# 1-Schematic_biz-card.net
KiCad netlist of a schematic drawn in EasyEDA
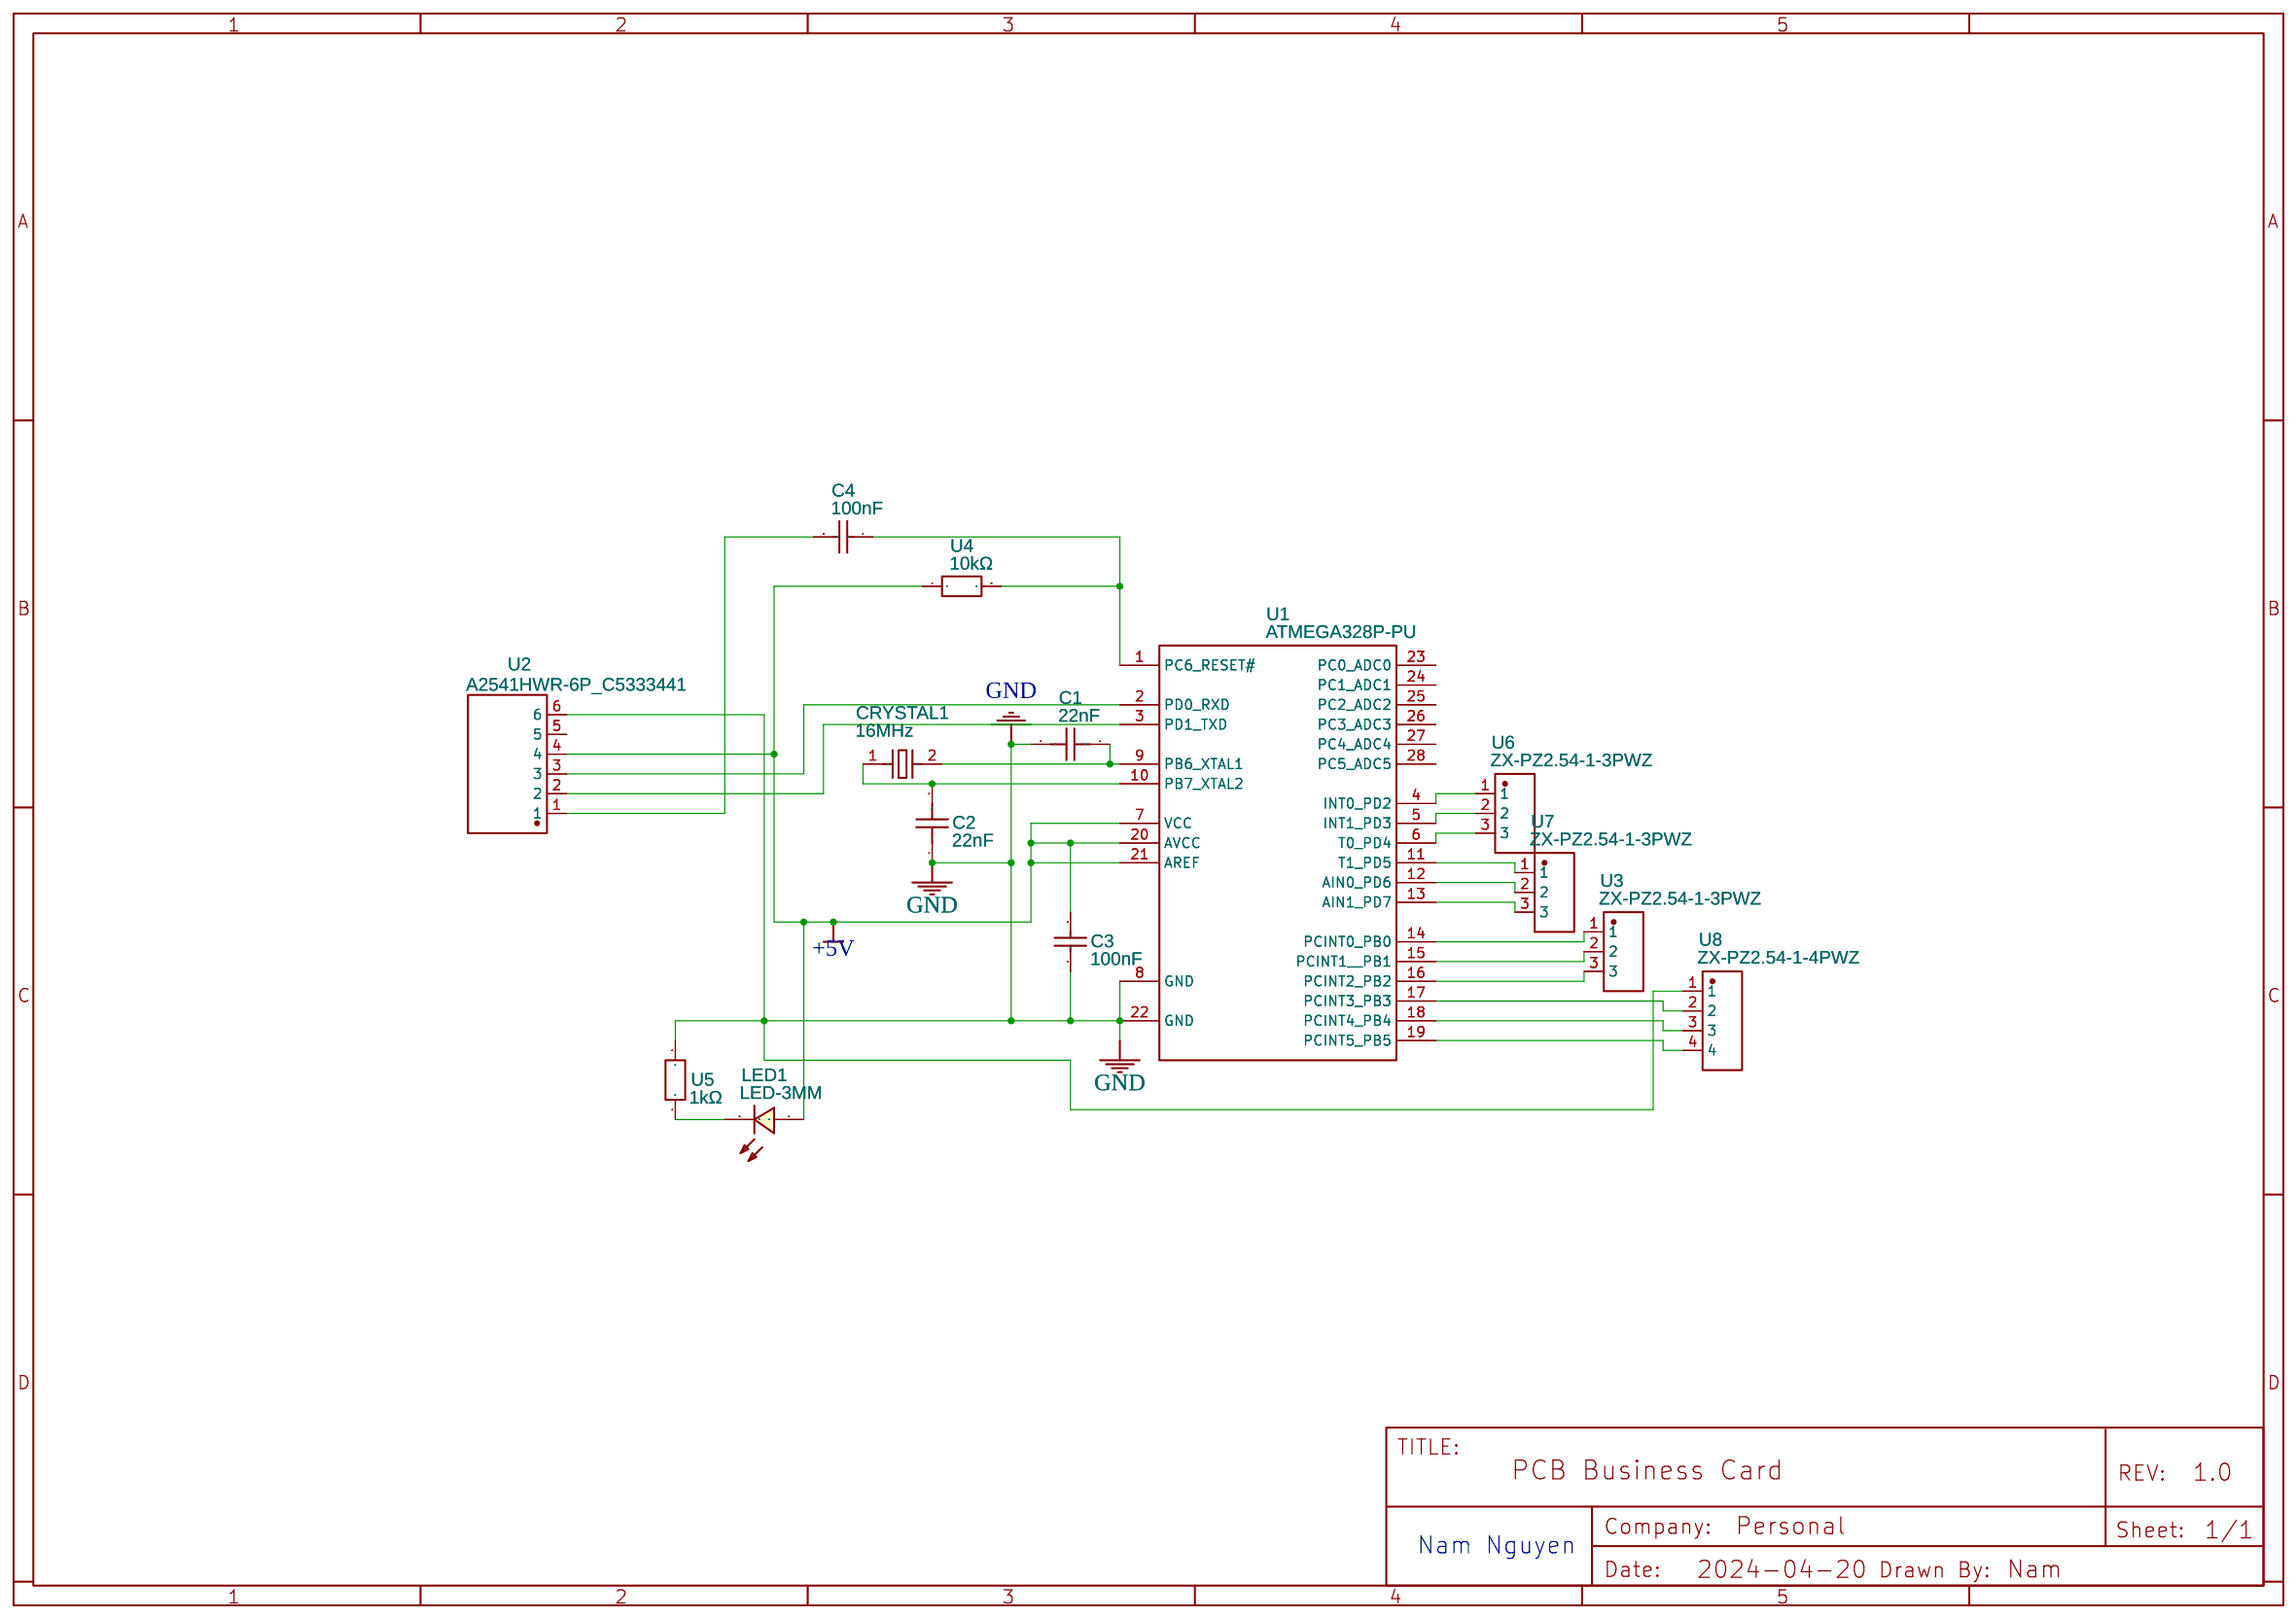
[diagram p0: schematic sheet]

(export (version "E")
  (design (tool "Eeschema 10.0.6"))
  (components
    (comp (ref "C1")
      (value "22nF")
      (fields
        (field (name "Manufacturer Part") "CC1H223ZC1SD3F4D30MF")
        (field (name "Manufacturer") "Dersonic(德尔创)")
      )
      (libsource (lib "") (part "CC1H223ZC1SD3F4D30MF_1"))
    )
    (comp (ref "C2")
      (value "22nF")
      (fields
        (field (name "Manufacturer Part") "CC1H223ZC1SD3F4D30MF")
        (field (name "Manufacturer") "Dersonic(德尔创)")
      )
      (libsource (lib "") (part "CC1H223ZC1SD3F4D30MF"))
    )
    (comp (ref "C3")
      (value "100nF")
      (fields (field (name "Manufacturer Part") "0.1UF(104) +-20% 63v"))
      (libsource (lib "") (part "100nF_1"))
    )
    (comp (ref "C4")
      (value "100nF")
      (fields (field (name "Manufacturer Part") "0.1UF(104) +-20% 63v"))
      (libsource (lib "") (part "100nF"))
    )
    (comp (ref "CRYSTAL1")
      (value "16MHz")
      (fields (field (name "Manufacturer Part") "SP2016M00020001") (field (name "Manufacturer") "HUAXIN(华昕)"))
      (libsource (lib "") (part "SP2016M00020001"))
    )
    (comp (ref "LED1")
      (value "LED-3MM")
      (fields (field (name "Manufacturer Part") "LED-3mm红"))
      (libsource (lib "") (part "LED-3MM红"))
    )
    (comp (ref "U1")
      (value "ATMEGA328P-PU")
      (fields (field (name "Manufacturer") "MICROCHIP(美国微芯)"))
      (libsource (lib "") (part "ATMEGA328P-PU"))
    )
    (comp (ref "U2")
      (value "A2541HWR-6P_C5333441")
      (fields (field (name "Manufacturer Part") "A2541HWR-6P") (field (name "Manufacturer") "CJT(长江连接器)"))
      (libsource (lib "") (part "A2541HWR-6P_C5333441"))
    )
    (comp (ref "U3")
      (value "ZX-PZ2.54-1-3PWZ")
      (fields (field (name "Manufacturer") "Megastar(兆星)"))
      (libsource (lib "") (part "ZX-PZ2.54-1-3PWZ"))
    )
    (comp (ref "U4")
      (value "10kΩ")
      (fields
        (field (name "Manufacturer Part") "RNS1FTD10K0")
        (field (name "Manufacturer") "SEI(Stackpole Electronics Inc.)")
      )
      (libsource (lib "") (part "RNS1FTD10K0"))
    )
    (comp (ref "U5")
      (value "1kΩ")
      (fields
        (field (name "Manufacturer Part") "MRS25000C1001FCT00")
        (field (name "Manufacturer") "VISHAY(威世)")
      )
      (libsource (lib "") (part "MRS25000C1001FCT00"))
    )
    (comp (ref "U6")
      (value "ZX-PZ2.54-1-3PWZ")
      (fields (field (name "Manufacturer") "Megastar(兆星)"))
      (libsource (lib "") (part "ZX-PZ2.54-1-3PWZ"))
    )
    (comp (ref "U7")
      (value "ZX-PZ2.54-1-3PWZ")
      (fields (field (name "Manufacturer") "Megastar(兆星)"))
      (libsource (lib "") (part "ZX-PZ2.54-1-3PWZ"))
    )
    (comp (ref "U8")
      (value "ZX-PZ2.54-1-4PWZ")
      (fields (field (name "Manufacturer") "Megastar(兆星)"))
      (libsource (lib "") (part "ZX-PZ2.54-1-4PWZ"))
    )
  )
  (nets
    (net (code "1") (name "+5V") (class "Default")
      (node (ref "C3") (pin "2") (pinfunction "2_2") (pintype "input"))
      (node (ref "LED1") (pin "1") (pinfunction "1_1") (pintype "unspecified"))
      (node (ref "U1") (pin "20") (pinfunction "AVCC_20") (pintype "passive"))
      (node (ref "U1") (pin "21") (pinfunction "AREF_21") (pintype "passive"))
      (node (ref "U1") (pin "7") (pinfunction "VCC_7") (pintype "passive"))
      (node (ref "U2") (pin "4") (pinfunction "4_4") (pintype "unspecified"))
      (node (ref "U4") (pin "1") (pinfunction "1_1") (pintype "unspecified"))
    )
    (net (code "2") (name "GND") (class "Default")
      (node (ref "C1") (pin "2") (pinfunction "2_2") (pintype "unspecified"))
      (node (ref "C2") (pin "1") (pinfunction "1_1") (pintype "unspecified"))
      (node (ref "C3") (pin "1") (pinfunction "1_1") (pintype "input"))
      (node (ref "U1") (pin "22") (pinfunction "GND_22") (pintype "passive"))
      (node (ref "U1") (pin "8") (pinfunction "GND_8") (pintype "passive"))
      (node (ref "U2") (pin "6") (pinfunction "6_6") (pintype "unspecified"))
      (node (ref "U5") (pin "2") (pinfunction "2_2") (pintype "unspecified"))
      (node (ref "U8") (pin "1") (pinfunction "1_1") (pintype "unspecified"))
    )
    (net (code "3") (name "Net-(C4-Pad2)") (class "Default")
      (node (ref "C4") (pin "2") (pinfunction "2_2") (pintype "input"))
      (node (ref "U2") (pin "1") (pinfunction "1_1") (pintype "unspecified"))
    )
    (net (code "4") (name "Net-(LED1-Pad2)") (class "Default")
      (node (ref "LED1") (pin "2") (pinfunction "2_2") (pintype "unspecified"))
      (node (ref "U5") (pin "1") (pinfunction "1_1") (pintype "unspecified"))
    )
    (net (code "5") (name "Net-(U1-AIN0_PD6)") (class "Default")
      (node (ref "U1") (pin "12") (pinfunction "AIN0_PD6_12") (pintype "bidirectional"))
      (node (ref "U7") (pin "2") (pinfunction "2_2") (pintype "unspecified"))
    )
    (net (code "6") (name "Net-(U1-AIN1_PD7)") (class "Default")
      (node (ref "U1") (pin "13") (pinfunction "AIN1_PD7_13") (pintype "bidirectional"))
      (node (ref "U7") (pin "3") (pinfunction "3_3") (pintype "unspecified"))
    )
    (net (code "7") (name "Net-(U1-INT0_PD2)") (class "Default")
      (node (ref "U1") (pin "4") (pinfunction "INT0_PD2_4") (pintype "bidirectional"))
      (node (ref "U6") (pin "1") (pinfunction "1_1") (pintype "unspecified"))
    )
    (net (code "8") (name "Net-(U1-INT1_PD3)") (class "Default")
      (node (ref "U1") (pin "5") (pinfunction "INT1_PD3_5") (pintype "bidirectional"))
      (node (ref "U6") (pin "2") (pinfunction "2_2") (pintype "unspecified"))
    )
    (net (code "9") (name "Net-(U1-PB6_XTAL1)") (class "Default")
      (node (ref "C1") (pin "1") (pinfunction "1_1") (pintype "unspecified"))
      (node (ref "CRYSTAL1") (pin "2") (pinfunction "2_2") (pintype "unspecified"))
      (node (ref "U1") (pin "9") (pinfunction "PB6_XTAL1_9") (pintype "bidirectional"))
    )
    (net (code "10") (name "Net-(U1-PB7_XTAL2)") (class "Default")
      (node (ref "C2") (pin "2") (pinfunction "2_2") (pintype "unspecified"))
      (node (ref "CRYSTAL1") (pin "1") (pinfunction "1_1") (pintype "unspecified"))
      (node (ref "U1") (pin "10") (pinfunction "PB7_XTAL2_10") (pintype "bidirectional"))
    )
    (net (code "11") (name "Net-(U1-PC6_RESET#)") (class "Default")
      (node (ref "C4") (pin "1") (pinfunction "1_1") (pintype "input"))
      (node (ref "U1") (pin "1") (pinfunction "PC6_RESET#_1") (pintype "bidirectional"))
      (node (ref "U4") (pin "2") (pinfunction "2_2") (pintype "unspecified"))
    )
    (net (code "12") (name "Net-(U1-PCINT0_PB0)") (class "Default")
      (node (ref "U1") (pin "14") (pinfunction "PCINT0_PB0_14") (pintype "bidirectional"))
      (node (ref "U3") (pin "1") (pinfunction "1_1") (pintype "unspecified"))
    )
    (net (code "13") (name "Net-(U1-PCINT1__PB1)") (class "Default")
      (node (ref "U1") (pin "15") (pinfunction "PCINT1__PB1_15") (pintype "bidirectional"))
      (node (ref "U3") (pin "2") (pinfunction "2_2") (pintype "unspecified"))
    )
    (net (code "14") (name "Net-(U1-PCINT2_PB2)") (class "Default")
      (node (ref "U1") (pin "16") (pinfunction "PCINT2_PB2_16") (pintype "bidirectional"))
      (node (ref "U3") (pin "3") (pinfunction "3_3") (pintype "unspecified"))
    )
    (net (code "15") (name "Net-(U1-PCINT3_PB3)") (class "Default")
      (node (ref "U1") (pin "17") (pinfunction "PCINT3_PB3_17") (pintype "bidirectional"))
      (node (ref "U8") (pin "2") (pinfunction "2_2") (pintype "unspecified"))
    )
    (net (code "16") (name "Net-(U1-PCINT4_PB4)") (class "Default")
      (node (ref "U1") (pin "18") (pinfunction "PCINT4_PB4_18") (pintype "bidirectional"))
      (node (ref "U8") (pin "3") (pinfunction "3_3") (pintype "unspecified"))
    )
    (net (code "17") (name "Net-(U1-PCINT5_PB5)") (class "Default")
      (node (ref "U1") (pin "19") (pinfunction "PCINT5_PB5_19") (pintype "bidirectional"))
      (node (ref "U8") (pin "4") (pinfunction "4_4") (pintype "unspecified"))
    )
    (net (code "18") (name "Net-(U1-PD0_RXD)") (class "Default")
      (node (ref "U1") (pin "2") (pinfunction "PD0_RXD_2") (pintype "bidirectional"))
      (node (ref "U2") (pin "3") (pinfunction "3_3") (pintype "unspecified"))
    )
    (net (code "19") (name "Net-(U1-PD1_TXD)") (class "Default")
      (node (ref "U1") (pin "3") (pinfunction "PD1_TXD_3") (pintype "bidirectional"))
      (node (ref "U2") (pin "2") (pinfunction "2_2") (pintype "unspecified"))
    )
    (net (code "20") (name "Net-(U1-T0_PD4)") (class "Default")
      (node (ref "U1") (pin "6") (pinfunction "T0_PD4_6") (pintype "bidirectional"))
      (node (ref "U6") (pin "3") (pinfunction "3_3") (pintype "unspecified"))
    )
    (net (code "21") (name "Net-(U1-T1_PD5)") (class "Default")
      (node (ref "U1") (pin "11") (pinfunction "T1_PD5_11") (pintype "bidirectional"))
      (node (ref "U7") (pin "1") (pinfunction "1_1") (pintype "unspecified"))
    )
    (net (code "22") (name "unconnected-(U1-PC0_ADC0-Pad23)") (class "Default")
      (node (ref "U1") (pin "23") (pinfunction "PC0_ADC0_23") (pintype "bidirectional"))
    )
    (net (code "23") (name "unconnected-(U1-PC1_ADC1-Pad24)") (class "Default")
      (node (ref "U1") (pin "24") (pinfunction "PC1_ADC1_24") (pintype "bidirectional"))
    )
    (net (code "24") (name "unconnected-(U1-PC2_ADC2-Pad25)") (class "Default")
      (node (ref "U1") (pin "25") (pinfunction "PC2_ADC2_25") (pintype "bidirectional"))
    )
    (net (code "25") (name "unconnected-(U1-PC3_ADC3-Pad26)") (class "Default")
      (node (ref "U1") (pin "26") (pinfunction "PC3_ADC3_26") (pintype "bidirectional"))
    )
    (net (code "26") (name "unconnected-(U1-PC4_ADC4-Pad27)") (class "Default")
      (node (ref "U1") (pin "27") (pinfunction "PC4_ADC4_27") (pintype "bidirectional"))
    )
    (net (code "27") (name "unconnected-(U1-PC5_ADC5-Pad28)") (class "Default")
      (node (ref "U1") (pin "28") (pinfunction "PC5_ADC5_28") (pintype "bidirectional"))
    )
    (net (code "28") (name "unconnected-(U2-Pad5)") (class "Default")
      (node (ref "U2") (pin "5") (pinfunction "5_5") (pintype "unspecified"))
    )
  )
)
